# 06_WS2812.net
KiCad netlist of a schematic drawn in Altium Designer
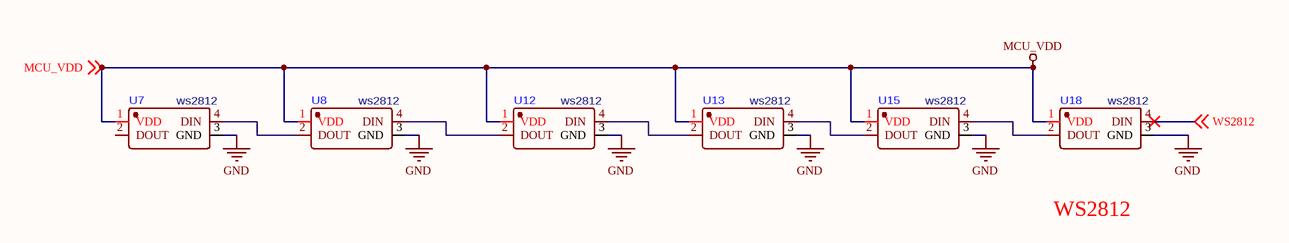
[diagram p0: 06_WS2812.SchDoc]

(export (version "E")
  (design (tool "Eeschema 10.0.6"))
  (components
    (comp (ref "U7")
      (value "ws2812")
      (footprint "WS2812B(3528)")
      (description "ws2812_3528")
      (libsource (lib "altium-import") (part "root_0_YOTC-WS2812B-3528_"))
    )
    (comp (ref "U8")
      (value "ws2812")
      (footprint "WS2812B(3528)")
      (description "ws2812_3528")
      (libsource (lib "altium-import") (part "root_0_YOTC-WS2812B-3528_"))
    )
    (comp (ref "U12")
      (value "ws2812")
      (footprint "WS2812B(3528)")
      (description "ws2812_3528")
      (libsource (lib "altium-import") (part "root_0_YOTC-WS2812B-3528_"))
    )
    (comp (ref "U13")
      (value "ws2812")
      (footprint "WS2812B(3528)")
      (description "ws2812_3528")
      (libsource (lib "altium-import") (part "root_0_YOTC-WS2812B-3528_"))
    )
    (comp (ref "U15")
      (value "ws2812")
      (footprint "WS2812B(3528)")
      (description "ws2812_3528")
      (libsource (lib "altium-import") (part "root_0_YOTC-WS2812B-3528_"))
    )
    (comp (ref "U18")
      (value "ws2812")
      (footprint "WS2812B(3528)")
      (description "ws2812_3528")
      (libsource (lib "altium-import") (part "root_0_YOTC-WS2812B-3528_"))
    )
  )
  (nets
    (net (code "1") (name "GND") (class "Default")
      (node (ref "U12") (pin "3") (pinfunction "GND_3") (pintype "passive"))
      (node (ref "U13") (pin "3") (pinfunction "GND_3") (pintype "passive"))
      (node (ref "U15") (pin "3") (pinfunction "GND_3") (pintype "passive"))
      (node (ref "U18") (pin "3") (pinfunction "GND_3") (pintype "passive"))
      (node (ref "U7") (pin "3") (pinfunction "GND_3") (pintype "passive"))
      (node (ref "U8") (pin "3") (pinfunction "GND_3") (pintype "passive"))
    )
    (net (code "2") (name "MCU_VDD") (class "Default")
      (node (ref "U12") (pin "1") (pinfunction "VDD_1") (pintype "passive"))
      (node (ref "U13") (pin "1") (pinfunction "VDD_1") (pintype "passive"))
      (node (ref "U15") (pin "1") (pinfunction "VDD_1") (pintype "passive"))
      (node (ref "U18") (pin "1") (pinfunction "VDD_1") (pintype "passive"))
      (node (ref "U7") (pin "1") (pinfunction "VDD_1") (pintype "passive"))
      (node (ref "U8") (pin "1") (pinfunction "VDD_1") (pintype "passive"))
    )
    (net (code "3") (name "Net-(U7-DIN)") (class "Default")
      (node (ref "U7") (pin "4") (pinfunction "DIN_4") (pintype "passive"))
      (node (ref "U8") (pin "2") (pinfunction "DOUT_2") (pintype "passive"))
    )
    (net (code "4") (name "Net-(U12-DIN)") (class "Default")
      (node (ref "U12") (pin "4") (pinfunction "DIN_4") (pintype "passive"))
      (node (ref "U13") (pin "2") (pinfunction "DOUT_2") (pintype "passive"))
    )
    (net (code "5") (name "Net-(U12-DOUT)") (class "Default")
      (node (ref "U12") (pin "2") (pinfunction "DOUT_2") (pintype "passive"))
      (node (ref "U8") (pin "4") (pinfunction "DIN_4") (pintype "passive"))
    )
    (net (code "6") (name "Net-(U13-DIN)") (class "Default")
      (node (ref "U13") (pin "4") (pinfunction "DIN_4") (pintype "passive"))
      (node (ref "U15") (pin "2") (pinfunction "DOUT_2") (pintype "passive"))
    )
    (net (code "7") (name "Net-(U15-DIN)") (class "Default")
      (node (ref "U15") (pin "4") (pinfunction "DIN_4") (pintype "passive"))
      (node (ref "U18") (pin "2") (pinfunction "DOUT_2") (pintype "passive"))
    )
    (net (code "8") (name "WS2812") (class "Default")
      (node (ref "U18") (pin "4") (pinfunction "DIN_4") (pintype "passive"))
    )
    (net (code "9") (name "unconnected-(U7-DOUT-Pad2)") (class "Default")
      (node (ref "U7") (pin "2") (pinfunction "DOUT_2") (pintype "passive"))
    )
  )
)
